# Booster_Main_Board.net
KiCad netlist of a schematic drawn in Altium Designer
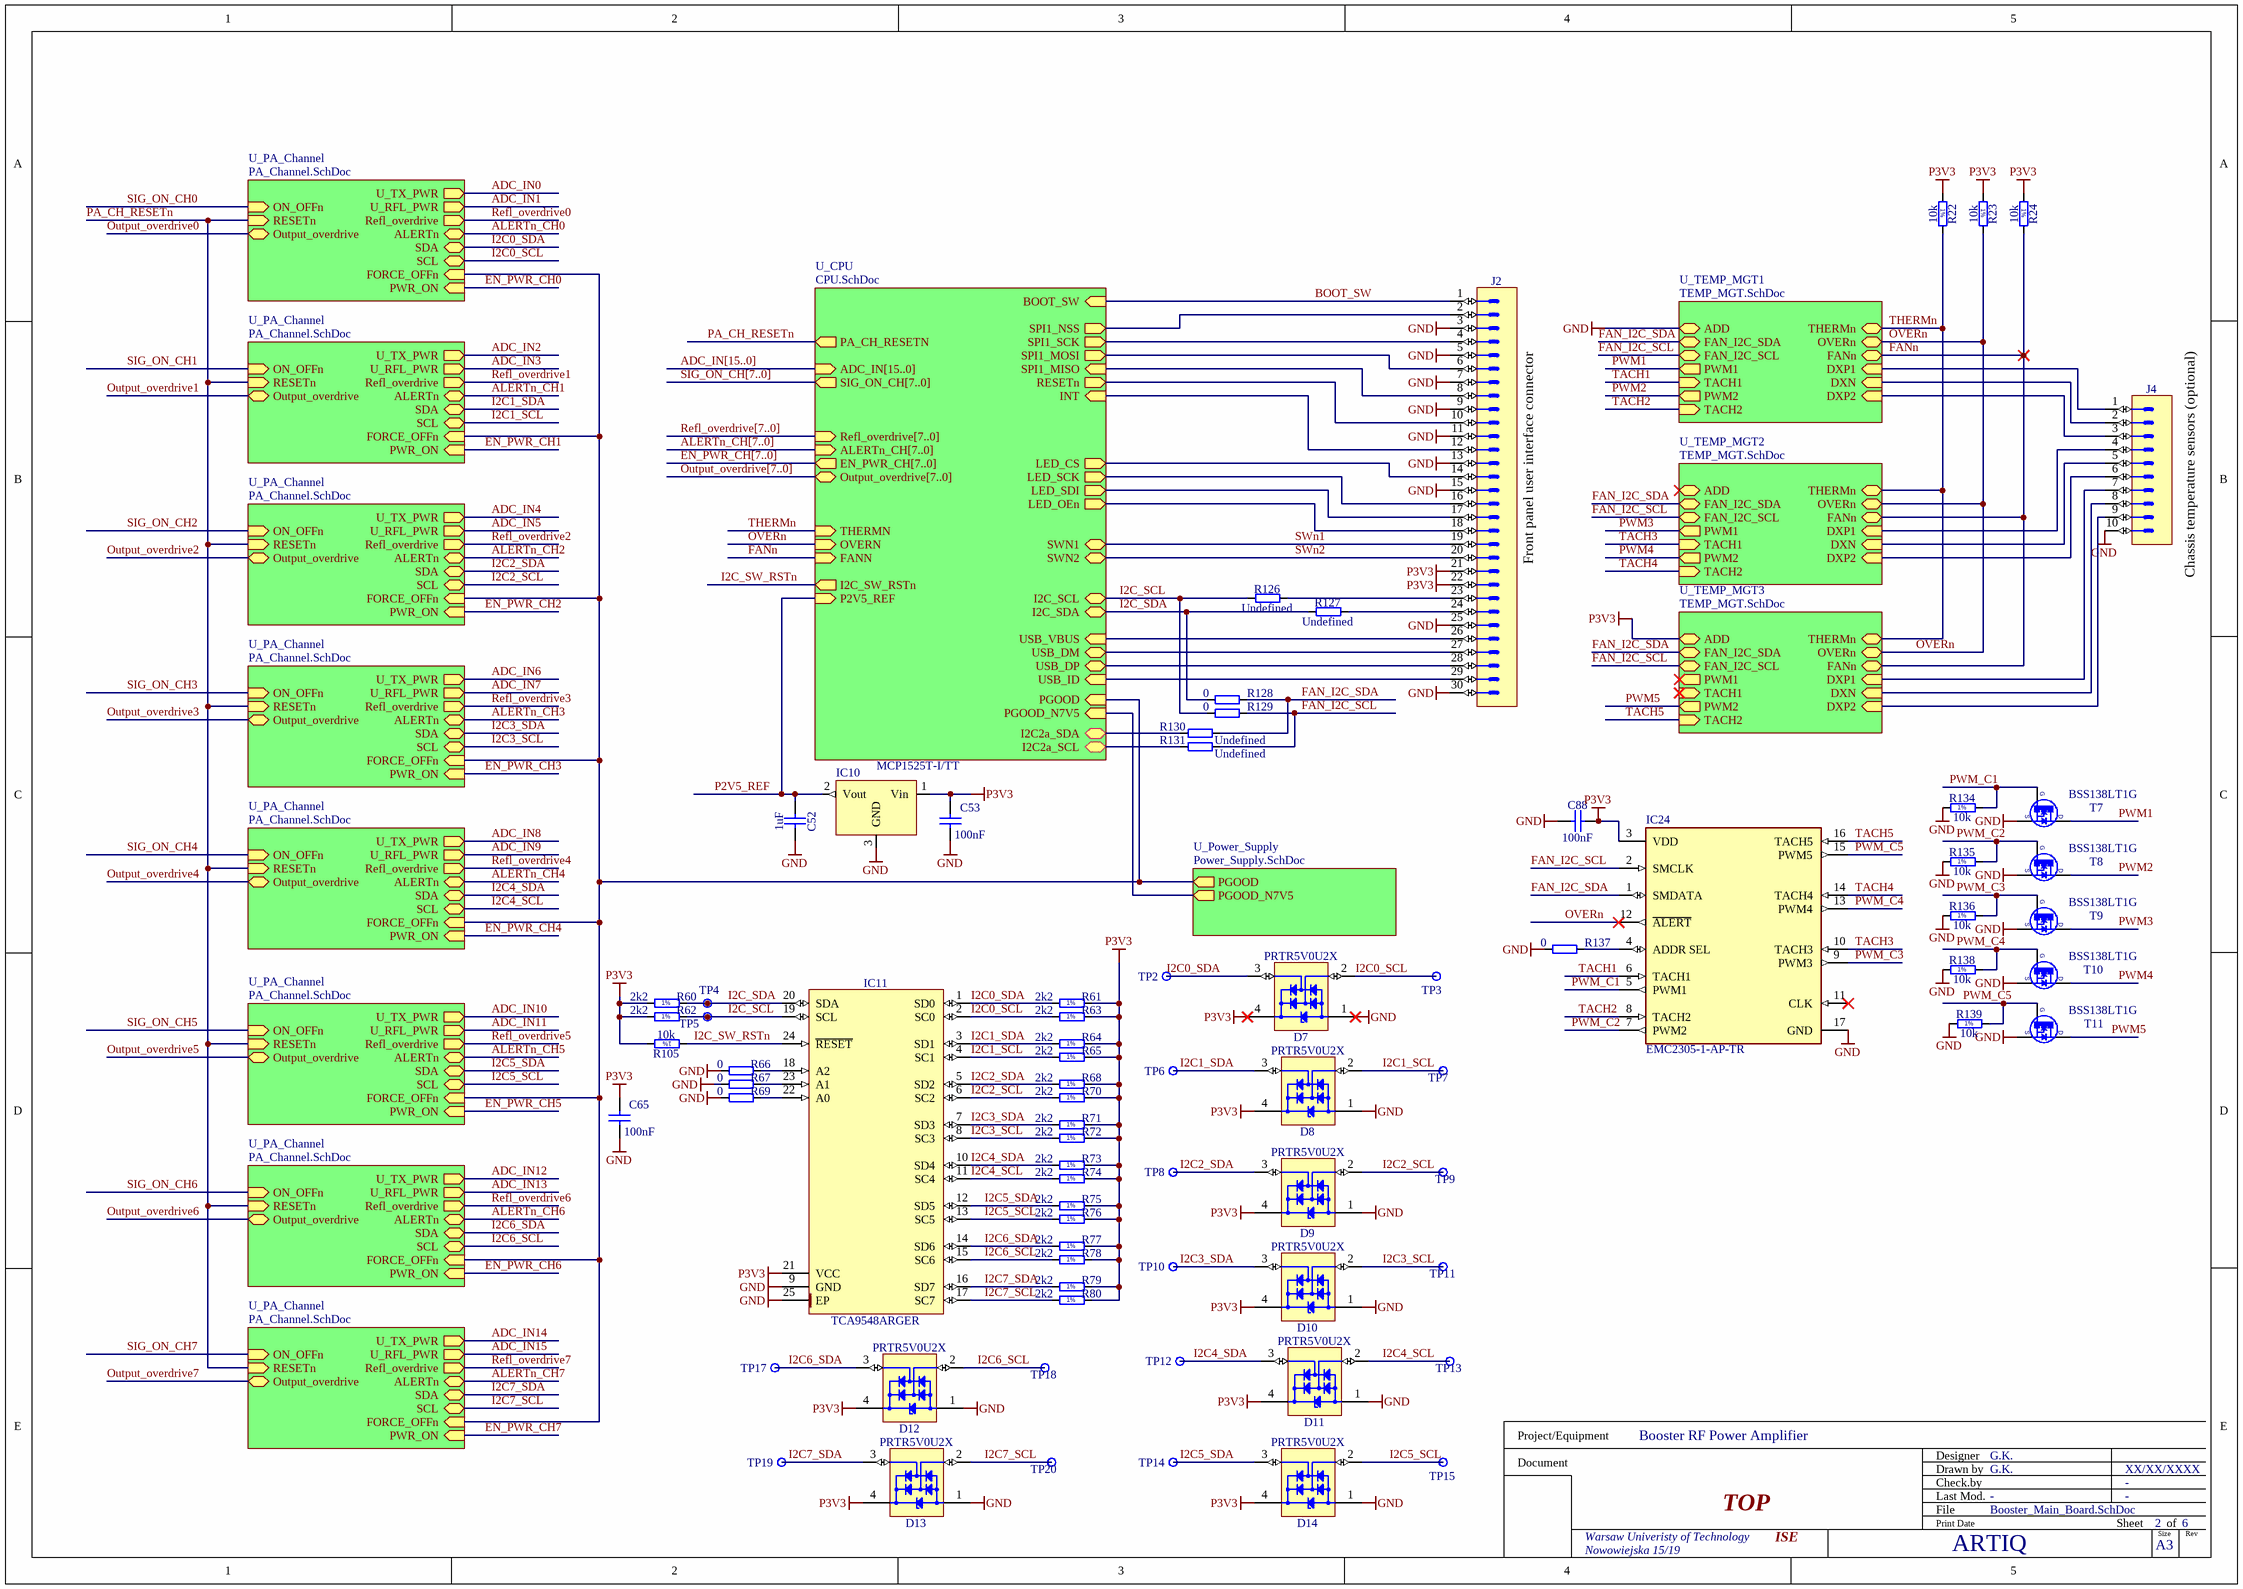
[diagram p0: Booster_Main_Board.SchDoc]

(export (version "E")
  (design (tool "Eeschema 10.0.6"))
  (components
    (comp (ref "C52")
      (value "1uF")
      (footprint "CAPC1005X55N")
      (description "Non-polarised capacitor")
      (fields
        (field (name "PART NUMBER") "CC0402_1UF_16V_10%_X5R")
        (field (name "VOLTAGE") "16V")
        (field (name "AUTHOR") "CERN DEM JLC")
      )
      (libsource (lib "Capacitors") (part "Capacitor - non polarized"))
    )
    (comp (ref "C53")
      (value "100nF")
      (footprint "CAPC1005X55N")
      (description "Non-polarised capacitor")
      (fields
        (field (name "PART NUMBER") "CC0402_100NF_16V_10%_X7R")
        (field (name "VOLTAGE") "16V")
        (field (name "AUTHOR") "CERN DEM JLC")
      )
      (libsource (lib "Capacitors") (part "Capacitor - non polarized"))
    )
    (comp (ref "C65")
      (value "100nF")
      (footprint "CAPC1005X55N")
      (description "Non-polarised capacitor")
      (fields
        (field (name "PART NUMBER") "CC0402_100NF_16V_10%_X7R")
        (field (name "VOLTAGE") "16V")
        (field (name "AUTHOR") "CERN DEM JLC")
      )
      (libsource (lib "Capacitors") (part "Capacitor - non polarized"))
    )
    (comp (ref "C88")
      (value "100nF")
      (footprint "CAPC1005X55N")
      (description "Non-polarised capacitor")
      (fields
        (field (name "PART NUMBER") "CC0402_100NF_16V_10%_X7R")
        (field (name "VOLTAGE") "16V")
        (field (name "AUTHOR") "CERN DEM JLC")
      )
      (libsource (lib "Capacitors") (part "Capacitor - non polarized"))
    )
    (comp (ref "D7")
      (value "PRTR5V0U2X")
      (footprint "SOT190P230X110-4N")
      (description "Ultra Low Capacitance Double Rail-to-Rail ESD Protection Diode")
      (fields
        (field (name "VOLTAGE") "5.5V")
        (field (name "MANUFACTURER") "NXP SEMICONDUCTORS")
        (field (name "AUTHOR") "CERN DEM JLC")
      )
      (libsource (lib "ICs And Semiconductors") (part "PRTR5V0U2X"))
    )
    (comp (ref "D8")
      (value "PRTR5V0U2X")
      (footprint "SOT190P230X110-4N")
      (description "Ultra Low Capacitance Double Rail-to-Rail ESD Protection Diode")
      (fields
        (field (name "VOLTAGE") "5.5V")
        (field (name "MANUFACTURER") "NXP SEMICONDUCTORS")
        (field (name "AUTHOR") "CERN DEM JLC")
      )
      (libsource (lib "ICs And Semiconductors") (part "PRTR5V0U2X"))
    )
    (comp (ref "D9")
      (value "PRTR5V0U2X")
      (footprint "SOT190P230X110-4N")
      (description "Ultra Low Capacitance Double Rail-to-Rail ESD Protection Diode")
      (fields
        (field (name "VOLTAGE") "5.5V")
        (field (name "MANUFACTURER") "NXP SEMICONDUCTORS")
        (field (name "AUTHOR") "CERN DEM JLC")
      )
      (libsource (lib "ICs And Semiconductors") (part "PRTR5V0U2X"))
    )
    (comp (ref "D10")
      (value "PRTR5V0U2X")
      (footprint "SOT190P230X110-4N")
      (description "Ultra Low Capacitance Double Rail-to-Rail ESD Protection Diode")
      (fields
        (field (name "VOLTAGE") "5.5V")
        (field (name "MANUFACTURER") "NXP SEMICONDUCTORS")
        (field (name "AUTHOR") "CERN DEM JLC")
      )
      (libsource (lib "ICs And Semiconductors") (part "PRTR5V0U2X"))
    )
    (comp (ref "D11")
      (value "PRTR5V0U2X")
      (footprint "SOT190P230X110-4N")
      (description "Ultra Low Capacitance Double Rail-to-Rail ESD Protection Diode")
      (fields
        (field (name "VOLTAGE") "5.5V")
        (field (name "MANUFACTURER") "NXP SEMICONDUCTORS")
        (field (name "AUTHOR") "CERN DEM JLC")
      )
      (libsource (lib "ICs And Semiconductors") (part "PRTR5V0U2X"))
    )
    (comp (ref "D12")
      (value "PRTR5V0U2X")
      (footprint "SOT190P230X110-4N")
      (description "Ultra Low Capacitance Double Rail-to-Rail ESD Protection Diode")
      (fields
        (field (name "VOLTAGE") "5.5V")
        (field (name "MANUFACTURER") "NXP SEMICONDUCTORS")
        (field (name "AUTHOR") "CERN DEM JLC")
      )
      (libsource (lib "ICs And Semiconductors") (part "PRTR5V0U2X"))
    )
    (comp (ref "D13")
      (value "PRTR5V0U2X")
      (footprint "SOT190P230X110-4N")
      (description "Ultra Low Capacitance Double Rail-to-Rail ESD Protection Diode")
      (fields
        (field (name "VOLTAGE") "5.5V")
        (field (name "MANUFACTURER") "NXP SEMICONDUCTORS")
        (field (name "AUTHOR") "CERN DEM JLC")
      )
      (libsource (lib "ICs And Semiconductors") (part "PRTR5V0U2X"))
    )
    (comp (ref "D14")
      (value "PRTR5V0U2X")
      (footprint "SOT190P230X110-4N")
      (description "Ultra Low Capacitance Double Rail-to-Rail ESD Protection Diode")
      (fields
        (field (name "VOLTAGE") "5.5V")
        (field (name "MANUFACTURER") "NXP SEMICONDUCTORS")
        (field (name "AUTHOR") "CERN DEM JLC")
      )
      (libsource (lib "ICs And Semiconductors") (part "PRTR5V0U2X"))
    )
    (comp (ref "IC10")
      (value "MCP1525T-I/TT")
      (footprint "SOT95P251X112-3N")
      (description "2.5 voltage reference")
      (libsource (lib "LIBRARY_SCH") (part "REF_MCP1525"))
    )
    (comp (ref "IC11")
      (value "TCA9548ARGER")
      (footprint "QFN50P400X400X100-25N-S220")
      (description "Low Voltage 8-Channel I2C Switch With Reset")
      (fields (field (name "MANUFACTURER") "TEXAS INSTRUMENTS") (field (name "AUTHOR") "CERN DEM JLC"))
      (libsource (lib "ICs And Semiconductors") (part "TCA9548ARGER"))
    )
    (comp (ref "IC24")
      (value "EMC2305-1-AP-TR")
      (footprint "FP-EMC2305-1-AP-TR-MFG")
      (description "IC MOTOR DRIVER 3V-3.6V 16QFN")
      (libsource (lib "Altium Content Vault") (part "344f2bb6cacff359c8bcd9507a07fb2"))
    )
    (comp (ref "J2")
      (value "~")
      (footprint "3M_N2530-6002RB")
      (description "Connector 30 Male")
      (fields
        (field (name "PART NUMBER") "3M_N2530-6002RB")
        (field (name "MANUFACTURER") "3M")
        (field (name "AUTHOR") "CERN DEM JLC")
      )
      (libsource (lib "Connectors") (part "Connector 30 Male"))
    )
    (comp (ref "J4")
      (value "Header 10")
      (footprint "3M_N2510-6003RB")
      (description "Connector 10 Male")
      (fields
        (field (name "PART NUMBER") "3M_N2510-6003RB")
        (field (name "MANUFACTURER") "3M")
        (field (name "AUTHOR") "CERN DEM JLC")
      )
      (libsource (lib "Connectors") (part "Connector 10 Male"))
    )
    (comp (ref "R22")
      (value "10k")
      (footprint "RESC1005X40N")
      (description "Resistor - 1%")
      (fields
        (field (name "PART NUMBER") "R0402_10K_1%_0.0625W_100PPM")
        (field (name "POWER") "0.0625W")
        (field (name "AUTHOR") "CERN DEM JLC")
      )
      (libsource (lib "Resistors") (part "Resistor - 1%"))
    )
    (comp (ref "R23")
      (value "10k")
      (footprint "RESC1005X40N")
      (description "Resistor - 1%")
      (fields
        (field (name "PART NUMBER") "R0402_10K_1%_0.0625W_100PPM")
        (field (name "POWER") "0.0625W")
        (field (name "AUTHOR") "CERN DEM JLC")
      )
      (libsource (lib "Resistors") (part "Resistor - 1%"))
    )
    (comp (ref "R24")
      (value "10k")
      (footprint "RESC1005X40N")
      (description "Resistor - 1%")
      (fields
        (field (name "PART NUMBER") "R0402_10K_1%_0.0625W_100PPM")
        (field (name "POWER") "0.0625W")
        (field (name "AUTHOR") "CERN DEM JLC")
      )
      (libsource (lib "Resistors") (part "Resistor - 1%"))
    )
    (comp (ref "R60")
      (value "2k2")
      (footprint "RESC1005X40N")
      (description "Resistor - 1%")
      (fields
        (field (name "PART NUMBER") "R0402_2K2_1%_0.0625W_100PPM")
        (field (name "POWER") "0.0625W")
        (field (name "AUTHOR") "CERN DEM JLC")
      )
      (libsource (lib "Resistors") (part "Resistor - 1%"))
    )
    (comp (ref "R61")
      (value "2k2")
      (footprint "RESC1005X40N")
      (description "Resistor - 1%")
      (fields
        (field (name "PART NUMBER") "R0402_2K2_1%_0.0625W_100PPM")
        (field (name "POWER") "0.0625W")
        (field (name "AUTHOR") "CERN DEM JLC")
      )
      (libsource (lib "Resistors") (part "Resistor - 1%"))
    )
    (comp (ref "R62")
      (value "2k2")
      (footprint "RESC1005X40N")
      (description "Resistor - 1%")
      (fields
        (field (name "PART NUMBER") "R0402_2K2_1%_0.0625W_100PPM")
        (field (name "POWER") "0.0625W")
        (field (name "AUTHOR") "CERN DEM JLC")
      )
      (libsource (lib "Resistors") (part "Resistor - 1%"))
    )
    (comp (ref "R63")
      (value "2k2")
      (footprint "RESC1005X40N")
      (description "Resistor - 1%")
      (fields
        (field (name "PART NUMBER") "R0402_2K2_1%_0.0625W_100PPM")
        (field (name "POWER") "0.0625W")
        (field (name "AUTHOR") "CERN DEM JLC")
      )
      (libsource (lib "Resistors") (part "Resistor - 1%"))
    )
    (comp (ref "R64")
      (value "2k2")
      (footprint "RESC1005X40N")
      (description "Resistor - 1%")
      (fields
        (field (name "PART NUMBER") "R0402_2K2_1%_0.0625W_100PPM")
        (field (name "POWER") "0.0625W")
        (field (name "AUTHOR") "CERN DEM JLC")
      )
      (libsource (lib "Resistors") (part "Resistor - 1%"))
    )
    (comp (ref "R65")
      (value "2k2")
      (footprint "RESC1005X40N")
      (description "Resistor - 1%")
      (fields
        (field (name "PART NUMBER") "R0402_2K2_1%_0.0625W_100PPM")
        (field (name "POWER") "0.0625W")
        (field (name "AUTHOR") "CERN DEM JLC")
      )
      (libsource (lib "Resistors") (part "Resistor - 1%"))
    )
    (comp (ref "R66")
      (value "0")
      (footprint "RESC1005X40N")
      (description "Resistor")
      (fields
        (field (name "PART NUMBER") "R0402_0R_JUMPER")
        (field (name "MANUFACTURER") "GENERIC")
        (field (name "AUTHOR") "CERN DEM JLC")
      )
      (libsource (lib "Resistors") (part "Resistor"))
    )
    (comp (ref "R67")
      (value "0")
      (footprint "RESC1005X40N")
      (description "Resistor")
      (fields
        (field (name "PART NUMBER") "R0402_0R_JUMPER")
        (field (name "MANUFACTURER") "GENERIC")
        (field (name "AUTHOR") "CERN DEM JLC")
      )
      (libsource (lib "Resistors") (part "Resistor"))
    )
    (comp (ref "R68")
      (value "2k2")
      (footprint "RESC1005X40N")
      (description "Resistor - 1%")
      (fields
        (field (name "PART NUMBER") "R0402_2K2_1%_0.0625W_100PPM")
        (field (name "POWER") "0.0625W")
        (field (name "AUTHOR") "CERN DEM JLC")
      )
      (libsource (lib "Resistors") (part "Resistor - 1%"))
    )
    (comp (ref "R69")
      (value "0")
      (footprint "RESC1005X40N")
      (description "Resistor")
      (fields
        (field (name "PART NUMBER") "R0402_0R_JUMPER")
        (field (name "MANUFACTURER") "GENERIC")
        (field (name "AUTHOR") "CERN DEM JLC")
      )
      (libsource (lib "Resistors") (part "Resistor"))
    )
    (comp (ref "R70")
      (value "2k2")
      (footprint "RESC1005X40N")
      (description "Resistor - 1%")
      (fields
        (field (name "PART NUMBER") "R0402_2K2_1%_0.0625W_100PPM")
        (field (name "POWER") "0.0625W")
        (field (name "AUTHOR") "CERN DEM JLC")
      )
      (libsource (lib "Resistors") (part "Resistor - 1%"))
    )
    (comp (ref "R71")
      (value "2k2")
      (footprint "RESC1005X40N")
      (description "Resistor - 1%")
      (fields
        (field (name "PART NUMBER") "R0402_2K2_1%_0.0625W_100PPM")
        (field (name "POWER") "0.0625W")
        (field (name "AUTHOR") "CERN DEM JLC")
      )
      (libsource (lib "Resistors") (part "Resistor - 1%"))
    )
    (comp (ref "R72")
      (value "2k2")
      (footprint "RESC1005X40N")
      (description "Resistor - 1%")
      (fields
        (field (name "PART NUMBER") "R0402_2K2_1%_0.0625W_100PPM")
        (field (name "POWER") "0.0625W")
        (field (name "AUTHOR") "CERN DEM JLC")
      )
      (libsource (lib "Resistors") (part "Resistor - 1%"))
    )
    (comp (ref "R73")
      (value "2k2")
      (footprint "RESC1005X40N")
      (description "Resistor - 1%")
      (fields
        (field (name "PART NUMBER") "R0402_2K2_1%_0.0625W_100PPM")
        (field (name "POWER") "0.0625W")
        (field (name "AUTHOR") "CERN DEM JLC")
      )
      (libsource (lib "Resistors") (part "Resistor - 1%"))
    )
    (comp (ref "R74")
      (value "2k2")
      (footprint "RESC1005X40N")
      (description "Resistor - 1%")
      (fields
        (field (name "PART NUMBER") "R0402_2K2_1%_0.0625W_100PPM")
        (field (name "POWER") "0.0625W")
        (field (name "AUTHOR") "CERN DEM JLC")
      )
      (libsource (lib "Resistors") (part "Resistor - 1%"))
    )
    (comp (ref "R75")
      (value "2k2")
      (footprint "RESC1005X40N")
      (description "Resistor - 1%")
      (fields
        (field (name "PART NUMBER") "R0402_2K2_1%_0.0625W_100PPM")
        (field (name "POWER") "0.0625W")
        (field (name "AUTHOR") "CERN DEM JLC")
      )
      (libsource (lib "Resistors") (part "Resistor - 1%"))
    )
    (comp (ref "R76")
      (value "2k2")
      (footprint "RESC1005X40N")
      (description "Resistor - 1%")
      (fields
        (field (name "PART NUMBER") "R0402_2K2_1%_0.0625W_100PPM")
        (field (name "POWER") "0.0625W")
        (field (name "AUTHOR") "CERN DEM JLC")
      )
      (libsource (lib "Resistors") (part "Resistor - 1%"))
    )
    (comp (ref "R77")
      (value "2k2")
      (footprint "RESC1005X40N")
      (description "Resistor - 1%")
      (fields
        (field (name "PART NUMBER") "R0402_2K2_1%_0.0625W_100PPM")
        (field (name "POWER") "0.0625W")
        (field (name "AUTHOR") "CERN DEM JLC")
      )
      (libsource (lib "Resistors") (part "Resistor - 1%"))
    )
    (comp (ref "R78")
      (value "2k2")
      (footprint "RESC1005X40N")
      (description "Resistor - 1%")
      (fields
        (field (name "PART NUMBER") "R0402_2K2_1%_0.0625W_100PPM")
        (field (name "POWER") "0.0625W")
        (field (name "AUTHOR") "CERN DEM JLC")
      )
      (libsource (lib "Resistors") (part "Resistor - 1%"))
    )
    (comp (ref "R79")
      (value "2k2")
      (footprint "RESC1005X40N")
      (description "Resistor - 1%")
      (fields
        (field (name "PART NUMBER") "R0402_2K2_1%_0.0625W_100PPM")
        (field (name "POWER") "0.0625W")
        (field (name "AUTHOR") "CERN DEM JLC")
      )
      (libsource (lib "Resistors") (part "Resistor - 1%"))
    )
    (comp (ref "R80")
      (value "2k2")
      (footprint "RESC1005X40N")
      (description "Resistor - 1%")
      (fields
        (field (name "PART NUMBER") "R0402_2K2_1%_0.0625W_100PPM")
        (field (name "POWER") "0.0625W")
        (field (name "AUTHOR") "CERN DEM JLC")
      )
      (libsource (lib "Resistors") (part "Resistor - 1%"))
    )
    (comp (ref "R105")
      (value "10k")
      (footprint "RESC1005X40N")
      (description "Resistor - 1%")
      (fields
        (field (name "PART NUMBER") "R0402_10K_1%_0.0625W_100PPM")
        (field (name "POWER") "0.0625W")
        (field (name "AUTHOR") "CERN DEM JLC")
      )
      (libsource (lib "Resistors") (part "Resistor - 1%"))
    )
    (comp (ref "R126")
      (value "Undefined")
      (footprint "RESC1005X40N")
      (description "Resistor")
      (fields (field (name "PART NUMBER") "R0402_NO-VALUE") (field (name "AUTHOR") "CERN DEM JLC"))
      (libsource (lib "Resistors") (part "Resistor"))
    )
    (comp (ref "R127")
      (value "Undefined")
      (footprint "RESC1005X40N")
      (description "Resistor")
      (fields (field (name "PART NUMBER") "R0402_NO-VALUE") (field (name "AUTHOR") "CERN DEM JLC"))
      (libsource (lib "Resistors") (part "Resistor"))
    )
    (comp (ref "R128")
      (value "0")
      (footprint "RESC1005X40N")
      (description "Resistor")
      (fields
        (field (name "PART NUMBER") "R0402_0R_JUMPER")
        (field (name "MANUFACTURER") "GENERIC")
        (field (name "AUTHOR") "CERN DEM JLC")
      )
      (libsource (lib "Resistors") (part "Resistor"))
    )
    (comp (ref "R129")
      (value "0")
      (footprint "RESC1005X40N")
      (description "Resistor")
      (fields
        (field (name "PART NUMBER") "R0402_0R_JUMPER")
        (field (name "MANUFACTURER") "GENERIC")
        (field (name "AUTHOR") "CERN DEM JLC")
      )
      (libsource (lib "Resistors") (part "Resistor"))
    )
    (comp (ref "R130")
      (value "Undefined")
      (footprint "RESC1005X40N")
      (description "Resistor")
      (fields (field (name "PART NUMBER") "R0402_NO-VALUE") (field (name "AUTHOR") "CERN DEM JLC"))
      (libsource (lib "Resistors") (part "Resistor"))
    )
    (comp (ref "R131")
      (value "Undefined")
      (footprint "RESC1005X40N")
      (description "Resistor")
      (fields (field (name "PART NUMBER") "R0402_NO-VALUE") (field (name "AUTHOR") "CERN DEM JLC"))
      (libsource (lib "Resistors") (part "Resistor"))
    )
    (comp (ref "R134")
      (value "10k")
      (footprint "RESC1005X40N")
      (description "Resistor - 1%")
      (fields
        (field (name "PART NUMBER") "R0402_10K_1%_0.0625W_100PPM")
        (field (name "POWER") "0.0625W")
        (field (name "AUTHOR") "CERN DEM JLC")
      )
      (libsource (lib "Resistors") (part "Resistor - 1%"))
    )
    (comp (ref "R135")
      (value "10k")
      (footprint "RESC1005X40N")
      (description "Resistor - 1%")
      (fields
        (field (name "PART NUMBER") "R0402_10K_1%_0.0625W_100PPM")
        (field (name "POWER") "0.0625W")
        (field (name "AUTHOR") "CERN DEM JLC")
      )
      (libsource (lib "Resistors") (part "Resistor - 1%"))
    )
    (comp (ref "R136")
      (value "10k")
      (footprint "RESC1005X40N")
      (description "Resistor - 1%")
      (fields
        (field (name "PART NUMBER") "R0402_10K_1%_0.0625W_100PPM")
        (field (name "POWER") "0.0625W")
        (field (name "AUTHOR") "CERN DEM JLC")
      )
      (libsource (lib "Resistors") (part "Resistor - 1%"))
    )
    (comp (ref "R137")
      (value "0")
      (footprint "RESC1005X40N")
      (description "Resistor")
      (fields
        (field (name "PART NUMBER") "R0402_0R_JUMPER")
        (field (name "MANUFACTURER") "GENERIC")
        (field (name "AUTHOR") "CERN DEM JLC")
      )
      (libsource (lib "Resistors") (part "Resistor"))
    )
    (comp (ref "R138")
      (value "10k")
      (footprint "RESC1005X40N")
      (description "Resistor - 1%")
      (fields
        (field (name "PART NUMBER") "R0402_10K_1%_0.0625W_100PPM")
        (field (name "POWER") "0.0625W")
        (field (name "AUTHOR") "CERN DEM JLC")
      )
      (libsource (lib "Resistors") (part "Resistor - 1%"))
    )
    (comp (ref "R139")
      (value "10k")
      (footprint "RESC1005X40N")
      (description "Resistor - 1%")
      (fields
        (field (name "PART NUMBER") "R0402_10K_1%_0.0625W_100PPM")
        (field (name "POWER") "0.0625W")
        (field (name "AUTHOR") "CERN DEM JLC")
      )
      (libsource (lib "Resistors") (part "Resistor - 1%"))
    )
    (comp (ref "T7")
      (value "BSS138LT1G")
      (footprint "SOT95P240X110-3N")
      (description "N-CHANNEL MOSFET WITH DIODE")
      (fields (field (name "MANUFACTURER") "ON SEMICONDUCTOR") (field (name "AUTHOR") "CERN DEM JLC"))
      (libsource (lib "ICs And Semiconductors") (part "N-MOSFET-D 1G 2S 3D"))
    )
    (comp (ref "T8")
      (value "BSS138LT1G")
      (footprint "SOT95P240X110-3N")
      (description "N-CHANNEL MOSFET WITH DIODE")
      (fields (field (name "MANUFACTURER") "ON SEMICONDUCTOR") (field (name "AUTHOR") "CERN DEM JLC"))
      (libsource (lib "ICs And Semiconductors") (part "N-MOSFET-D 1G 2S 3D"))
    )
    (comp (ref "T9")
      (value "BSS138LT1G")
      (footprint "SOT95P240X110-3N")
      (description "N-CHANNEL MOSFET WITH DIODE")
      (fields (field (name "MANUFACTURER") "ON SEMICONDUCTOR") (field (name "AUTHOR") "CERN DEM JLC"))
      (libsource (lib "ICs And Semiconductors") (part "N-MOSFET-D 1G 2S 3D"))
    )
    (comp (ref "T10")
      (value "BSS138LT1G")
      (footprint "SOT95P240X110-3N")
      (description "N-CHANNEL MOSFET WITH DIODE")
      (fields (field (name "MANUFACTURER") "ON SEMICONDUCTOR") (field (name "AUTHOR") "CERN DEM JLC"))
      (libsource (lib "ICs And Semiconductors") (part "N-MOSFET-D 1G 2S 3D"))
    )
    (comp (ref "T11")
      (value "BSS138LT1G")
      (footprint "SOT95P240X110-3N")
      (description "N-CHANNEL MOSFET WITH DIODE")
      (fields (field (name "MANUFACTURER") "ON SEMICONDUCTOR") (field (name "AUTHOR") "CERN DEM JLC"))
      (libsource (lib "ICs And Semiconductors") (part "N-MOSFET-D 1G 2S 3D"))
    )
    (comp (ref "TP2")
      (value "Test Point")
      (footprint "TPS127")
      (fields (field (name "PART NUMBER") "SMD_PAD_1.27X1.27MM") (field (name "AUTHOR") "CERN DEM JLC"))
      (libsource (lib "Eletro-mechanical") (part "Test Point"))
    )
    (comp (ref "TP3")
      (value "Test Point")
      (footprint "TPS127")
      (fields (field (name "PART NUMBER") "SMD_PAD_1.27X1.27MM") (field (name "AUTHOR") "CERN DEM JLC"))
      (libsource (lib "Eletro-mechanical") (part "Test Point"))
    )
    (comp (ref "TP4")
      (value "Test Point")
      (footprint "TPS127")
      (fields (field (name "PART NUMBER") "SMD_PAD_1.27X1.27MM") (field (name "AUTHOR") "CERN DEM JLC"))
      (libsource (lib "Eletro-mechanical") (part "Test Point"))
    )
    (comp (ref "TP5")
      (value "Test Point")
      (footprint "TPS127")
      (fields (field (name "PART NUMBER") "SMD_PAD_1.27X1.27MM") (field (name "AUTHOR") "CERN DEM JLC"))
      (libsource (lib "Eletro-mechanical") (part "Test Point"))
    )
    (comp (ref "TP6")
      (value "Test Point")
      (footprint "TPS127")
      (fields (field (name "PART NUMBER") "SMD_PAD_1.27X1.27MM") (field (name "AUTHOR") "CERN DEM JLC"))
      (libsource (lib "Eletro-mechanical") (part "Test Point"))
    )
    (comp (ref "TP7")
      (value "Test Point")
      (footprint "TPS127")
      (fields (field (name "PART NUMBER") "SMD_PAD_1.27X1.27MM") (field (name "AUTHOR") "CERN DEM JLC"))
      (libsource (lib "Eletro-mechanical") (part "Test Point"))
    )
    (comp (ref "TP8")
      (value "Test Point")
      (footprint "TPS127")
      (fields (field (name "PART NUMBER") "SMD_PAD_1.27X1.27MM") (field (name "AUTHOR") "CERN DEM JLC"))
      (libsource (lib "Eletro-mechanical") (part "Test Point"))
    )
    (comp (ref "TP9")
      (value "Test Point")
      (footprint "TPS127")
      (fields (field (name "PART NUMBER") "SMD_PAD_1.27X1.27MM") (field (name "AUTHOR") "CERN DEM JLC"))
      (libsource (lib "Eletro-mechanical") (part "Test Point"))
    )
    (comp (ref "TP10")
      (value "Test Point")
      (footprint "TPS127")
      (fields (field (name "PART NUMBER") "SMD_PAD_1.27X1.27MM") (field (name "AUTHOR") "CERN DEM JLC"))
      (libsource (lib "Eletro-mechanical") (part "Test Point"))
    )
    (comp (ref "TP11")
      (value "Test Point")
      (footprint "TPS127")
      (fields (field (name "PART NUMBER") "SMD_PAD_1.27X1.27MM") (field (name "AUTHOR") "CERN DEM JLC"))
      (libsource (lib "Eletro-mechanical") (part "Test Point"))
    )
    (comp (ref "TP12")
      (value "Test Point")
      (footprint "TPS127")
      (fields (field (name "PART NUMBER") "SMD_PAD_1.27X1.27MM") (field (name "AUTHOR") "CERN DEM JLC"))
      (libsource (lib "Eletro-mechanical") (part "Test Point"))
    )
    (comp (ref "TP13")
      (value "Test Point")
      (footprint "TPS127")
      (fields (field (name "PART NUMBER") "SMD_PAD_1.27X1.27MM") (field (name "AUTHOR") "CERN DEM JLC"))
      (libsource (lib "Eletro-mechanical") (part "Test Point"))
    )
    (comp (ref "TP14")
      (value "Test Point")
      (footprint "TPS127")
      (fields (field (name "PART NUMBER") "SMD_PAD_1.27X1.27MM") (field (name "AUTHOR") "CERN DEM JLC"))
      (libsource (lib "Eletro-mechanical") (part "Test Point"))
    )
    (comp (ref "TP15")
      (value "Test Point")
      (footprint "TPS127")
      (fields (field (name "PART NUMBER") "SMD_PAD_1.27X1.27MM") (field (name "AUTHOR") "CERN DEM JLC"))
      (libsource (lib "Eletro-mechanical") (part "Test Point"))
    )
    (comp (ref "TP17")
      (value "Test Point")
      (footprint "TPS127")
      (fields (field (name "PART NUMBER") "SMD_PAD_1.27X1.27MM") (field (name "AUTHOR") "CERN DEM JLC"))
      (libsource (lib "Eletro-mechanical") (part "Test Point"))
    )
    (comp (ref "TP18")
      (value "Test Point")
      (footprint "TPS127")
      (fields (field (name "PART NUMBER") "SMD_PAD_1.27X1.27MM") (field (name "AUTHOR") "CERN DEM JLC"))
      (libsource (lib "Eletro-mechanical") (part "Test Point"))
    )
    (comp (ref "TP19")
      (value "Test Point")
      (footprint "TPS127")
      (fields (field (name "PART NUMBER") "SMD_PAD_1.27X1.27MM") (field (name "AUTHOR") "CERN DEM JLC"))
      (libsource (lib "Eletro-mechanical") (part "Test Point"))
    )
    (comp (ref "TP20")
      (value "Test Point")
      (footprint "TPS127")
      (fields (field (name "PART NUMBER") "SMD_PAD_1.27X1.27MM") (field (name "AUTHOR") "CERN DEM JLC"))
      (libsource (lib "Eletro-mechanical") (part "Test Point"))
    )
  )
  (nets
    (net (code "28") (name "/BOOT_SW") (class "Default")
      (node (ref "J2") (pin "1") (pinfunction "1_1") (pintype "bidirectional"))
    )
    (net (code "29") (name "/DXN") (class "Default")
      (node (ref "J4") (pin "5") (pinfunction "5_5") (pintype "bidirectional"))
    )
    (net (code "30") (name "/DXN_1") (class "Default")
      (node (ref "J4") (pin "8") (pinfunction "8_8") (pintype "bidirectional"))
    )
    (net (code "31") (name "/DXN_2") (class "Default")
      (node (ref "J4") (pin "2") (pinfunction "2_2") (pintype "bidirectional"))
    )
    (net (code "32") (name "/DXP1") (class "Default")
      (node (ref "J4") (pin "4") (pinfunction "4_4") (pintype "bidirectional"))
    )
    (net (code "33") (name "/DXP1_1") (class "Default")
      (node (ref "J4") (pin "7") (pinfunction "7_7") (pintype "bidirectional"))
    )
    (net (code "34") (name "/DXP1_2") (class "Default")
      (node (ref "J4") (pin "1") (pinfunction "1_1") (pintype "bidirectional"))
    )
    (net (code "35") (name "/DXP2") (class "Default")
      (node (ref "J4") (pin "6") (pinfunction "6_6") (pintype "bidirectional"))
    )
    (net (code "36") (name "/DXP2_1") (class "Default")
      (node (ref "J4") (pin "9") (pinfunction "9_9") (pintype "bidirectional"))
    )
    (net (code "37") (name "/DXP2_2") (class "Default")
      (node (ref "J4") (pin "3") (pinfunction "3_3") (pintype "bidirectional"))
    )
    (net (code "47") (name "/FAN_I2C_SCL") (class "Default")
      (node (ref "IC24") (pin "2") (pinfunction "SMCLK_2") (pintype "input"))
      (node (ref "R129") (pin "2") (pinfunction "2_2") (pintype "passive"))
      (node (ref "R131") (pin "2") (pinfunction "2_2") (pintype "passive"))
    )
    (net (code "48") (name "/FAN_I2C_SDA") (class "Default")
      (node (ref "IC24") (pin "1") (pinfunction "SMDATA_1") (pintype "bidirectional"))
      (node (ref "R128") (pin "2") (pinfunction "2_2") (pintype "passive"))
      (node (ref "R130") (pin "2") (pinfunction "2_2") (pintype "passive"))
    )
    (net (code "49") (name "/FANn") (class "Default")
      (node (ref "R24") (pin "2") (pinfunction "2_2") (pintype "passive"))
    )
    (net (code "50") (name "/I2C0_SCL") (class "Default")
      (node (ref "D7") (pin "2") (pinfunction "I/O1_2") (pintype "bidirectional"))
      (node (ref "IC11") (pin "2") (pinfunction "SC0_2") (pintype "bidirectional"))
      (node (ref "R63") (pin "1") (pinfunction "1_1") (pintype "passive"))
      (node (ref "TP3") (pin "1") (pinfunction "1_1") (pintype "bidirectional"))
    )
    (net (code "51") (name "/I2C0_SDA") (class "Default")
      (node (ref "D7") (pin "3") (pinfunction "I/O2_3") (pintype "bidirectional"))
      (node (ref "IC11") (pin "1") (pinfunction "SD0_1") (pintype "bidirectional"))
      (node (ref "R61") (pin "1") (pinfunction "1_1") (pintype "passive"))
      (node (ref "TP2") (pin "1") (pinfunction "1_1") (pintype "bidirectional"))
    )
    (net (code "52") (name "/I2C1_SCL") (class "Default")
      (node (ref "D8") (pin "2") (pinfunction "I/O1_2") (pintype "bidirectional"))
      (node (ref "IC11") (pin "4") (pinfunction "SC1_4") (pintype "bidirectional"))
      (node (ref "R65") (pin "1") (pinfunction "1_1") (pintype "passive"))
      (node (ref "TP7") (pin "1") (pinfunction "1_1") (pintype "bidirectional"))
    )
    (net (code "53") (name "/I2C1_SDA") (class "Default")
      (node (ref "D8") (pin "3") (pinfunction "I/O2_3") (pintype "bidirectional"))
      (node (ref "IC11") (pin "3") (pinfunction "SD1_3") (pintype "bidirectional"))
      (node (ref "R64") (pin "1") (pinfunction "1_1") (pintype "passive"))
      (node (ref "TP6") (pin "1") (pinfunction "1_1") (pintype "bidirectional"))
    )
    (net (code "54") (name "/I2C2_SCL") (class "Default")
      (node (ref "D9") (pin "2") (pinfunction "I/O1_2") (pintype "bidirectional"))
      (node (ref "IC11") (pin "6") (pinfunction "SC2_6") (pintype "bidirectional"))
      (node (ref "R70") (pin "1") (pinfunction "1_1") (pintype "passive"))
      (node (ref "TP9") (pin "1") (pinfunction "1_1") (pintype "bidirectional"))
    )
    (net (code "55") (name "/I2C2_SDA") (class "Default")
      (node (ref "D9") (pin "3") (pinfunction "I/O2_3") (pintype "bidirectional"))
      (node (ref "IC11") (pin "5") (pinfunction "SD2_5") (pintype "bidirectional"))
      (node (ref "R68") (pin "1") (pinfunction "1_1") (pintype "passive"))
      (node (ref "TP8") (pin "1") (pinfunction "1_1") (pintype "bidirectional"))
    )
    (net (code "56") (name "/I2C2a_SCL") (class "Default")
      (node (ref "R131") (pin "1") (pinfunction "1_1") (pintype "passive"))
    )
    (net (code "57") (name "/I2C2a_SDA") (class "Default")
      (node (ref "R130") (pin "1") (pinfunction "1_1") (pintype "passive"))
    )
    (net (code "58") (name "/I2C3_SCL") (class "Default")
      (node (ref "D10") (pin "2") (pinfunction "I/O1_2") (pintype "bidirectional"))
      (node (ref "IC11") (pin "8") (pinfunction "SC3_8") (pintype "bidirectional"))
      (node (ref "R72") (pin "1") (pinfunction "1_1") (pintype "passive"))
      (node (ref "TP11") (pin "1") (pinfunction "1_1") (pintype "bidirectional"))
    )
    (net (code "59") (name "/I2C3_SDA") (class "Default")
      (node (ref "D10") (pin "3") (pinfunction "I/O2_3") (pintype "bidirectional"))
      (node (ref "IC11") (pin "7") (pinfunction "SD3_7") (pintype "bidirectional"))
      (node (ref "R71") (pin "1") (pinfunction "1_1") (pintype "passive"))
      (node (ref "TP10") (pin "1") (pinfunction "1_1") (pintype "bidirectional"))
    )
    (net (code "60") (name "/I2C4_SCL") (class "Default")
      (node (ref "D11") (pin "2") (pinfunction "I/O1_2") (pintype "bidirectional"))
      (node (ref "IC11") (pin "11") (pinfunction "SC4_11") (pintype "bidirectional"))
      (node (ref "R74") (pin "1") (pinfunction "1_1") (pintype "passive"))
      (node (ref "TP13") (pin "1") (pinfunction "1_1") (pintype "bidirectional"))
    )
    (net (code "61") (name "/I2C4_SDA") (class "Default")
      (node (ref "D11") (pin "3") (pinfunction "I/O2_3") (pintype "bidirectional"))
      (node (ref "IC11") (pin "10") (pinfunction "SD4_10") (pintype "bidirectional"))
      (node (ref "R73") (pin "1") (pinfunction "1_1") (pintype "passive"))
      (node (ref "TP12") (pin "1") (pinfunction "1_1") (pintype "bidirectional"))
    )
    (net (code "62") (name "/I2C5_SCL") (class "Default")
      (node (ref "D14") (pin "2") (pinfunction "I/O1_2") (pintype "bidirectional"))
      (node (ref "IC11") (pin "13") (pinfunction "SC5_13") (pintype "bidirectional"))
      (node (ref "R76") (pin "1") (pinfunction "1_1") (pintype "passive"))
      (node (ref "TP15") (pin "1") (pinfunction "1_1") (pintype "bidirectional"))
    )
    (net (code "63") (name "/I2C5_SDA") (class "Default")
      (node (ref "D14") (pin "3") (pinfunction "I/O2_3") (pintype "bidirectional"))
      (node (ref "IC11") (pin "12") (pinfunction "SD5_12") (pintype "bidirectional"))
      (node (ref "R75") (pin "1") (pinfunction "1_1") (pintype "passive"))
      (node (ref "TP14") (pin "1") (pinfunction "1_1") (pintype "bidirectional"))
    )
    (net (code "64") (name "/I2C6_SCL") (class "Default")
      (node (ref "D12") (pin "2") (pinfunction "I/O1_2") (pintype "bidirectional"))
      (node (ref "IC11") (pin "15") (pinfunction "SC6_15") (pintype "bidirectional"))
      (node (ref "R78") (pin "1") (pinfunction "1_1") (pintype "passive"))
      (node (ref "TP18") (pin "1") (pinfunction "1_1") (pintype "bidirectional"))
    )
    (net (code "65") (name "/I2C6_SDA") (class "Default")
      (node (ref "D12") (pin "3") (pinfunction "I/O2_3") (pintype "bidirectional"))
      (node (ref "IC11") (pin "14") (pinfunction "SD6_14") (pintype "bidirectional"))
      (node (ref "R77") (pin "1") (pinfunction "1_1") (pintype "passive"))
      (node (ref "TP17") (pin "1") (pinfunction "1_1") (pintype "bidirectional"))
    )
    (net (code "66") (name "/I2C7_SCL") (class "Default")
      (node (ref "D13") (pin "2") (pinfunction "I/O1_2") (pintype "bidirectional"))
      (node (ref "IC11") (pin "17") (pinfunction "SC7_17") (pintype "bidirectional"))
      (node (ref "R80") (pin "1") (pinfunction "1_1") (pintype "passive"))
      (node (ref "TP20") (pin "1") (pinfunction "1_1") (pintype "bidirectional"))
    )
    (net (code "67") (name "/I2C7_SDA") (class "Default")
      (node (ref "D13") (pin "3") (pinfunction "I/O2_3") (pintype "bidirectional"))
      (node (ref "IC11") (pin "16") (pinfunction "SD7_16") (pintype "bidirectional"))
      (node (ref "R79") (pin "1") (pinfunction "1_1") (pintype "passive"))
      (node (ref "TP19") (pin "1") (pinfunction "1_1") (pintype "bidirectional"))
    )
    (net (code "68") (name "/I2C_SCL") (class "Default")
      (node (ref "IC11") (pin "19") (pinfunction "SCL_19") (pintype "bidirectional"))
      (node (ref "R126") (pin "1") (pinfunction "1_1") (pintype "passive"))
      (node (ref "R129") (pin "1") (pinfunction "1_1") (pintype "passive"))
      (node (ref "R62") (pin "2") (pinfunction "2_2") (pintype "passive"))
      (node (ref "TP5") (pin "1") (pinfunction "1_1") (pintype "bidirectional"))
    )
    (net (code "69") (name "/I2C_SDA") (class "Default")
      (node (ref "IC11") (pin "20") (pinfunction "SDA_20") (pintype "bidirectional"))
      (node (ref "R127") (pin "1") (pinfunction "1_1") (pintype "passive"))
      (node (ref "R128") (pin "1") (pinfunction "1_1") (pintype "passive"))
      (node (ref "R60") (pin "2") (pinfunction "2_2") (pintype "passive"))
      (node (ref "TP4") (pin "1") (pinfunction "1_1") (pintype "bidirectional"))
    )
    (net (code "70") (name "/I2C_SW_RSTn") (class "Default")
      (node (ref "IC11") (pin "24") (pinfunction "~{RESET}_24") (pintype "input"))
      (node (ref "R105") (pin "1") (pinfunction "1_1") (pintype "passive"))
    )
    (net (code "71") (name "/INT") (class "Default")
      (node (ref "J2") (pin "12") (pinfunction "12_12") (pintype "bidirectional"))
    )
    (net (code "72") (name "/LED_CS") (class "Default")
      (node (ref "J2") (pin "14") (pinfunction "14_14") (pintype "bidirectional"))
    )
    (net (code "73") (name "/LED_OEn") (class "Default")
      (node (ref "J2") (pin "18") (pinfunction "18_18") (pintype "bidirectional"))
    )
    (net (code "74") (name "/LED_SCK") (class "Default")
      (node (ref "J2") (pin "16") (pinfunction "16_16") (pintype "bidirectional"))
    )
    (net (code "75") (name "/LED_SDI") (class "Default")
      (node (ref "J2") (pin "17") (pinfunction "17_17") (pintype "bidirectional"))
    )
    (net (code "76") (name "/OVERn") (class "Default")
      (node (ref "IC24") (pin "12") (pinfunction "~{ALERT}_12") (pintype "output"))
      (node (ref "R23") (pin "2") (pinfunction "2_2") (pintype "passive"))
    )
    (net (code "86") (name "/P2V5_REF") (class "Default")
      (node (ref "C52") (pin "1") (pinfunction "1_1") (pintype "passive"))
      (node (ref "IC10") (pin "2") (pinfunction "Vout_2") (pintype "output"))
    )
    (net (code "90") (name "/PWM1") (class "Default")
      (node (ref "T7") (pin "3") (pinfunction "D_3") (pintype "passive"))
    )
    (net (code "92") (name "/PWM2") (class "Default")
      (node (ref "T8") (pin "3") (pinfunction "D_3") (pintype "passive"))
    )
    (net (code "93") (name "/PWM3") (class "Default")
      (node (ref "T9") (pin "3") (pinfunction "D_3") (pintype "passive"))
    )
    (net (code "94") (name "/PWM4") (class "Default")
      (node (ref "T10") (pin "3") (pinfunction "D_3") (pintype "passive"))
    )
    (net (code "95") (name "/PWM5") (class "Default")
      (node (ref "T11") (pin "3") (pinfunction "D_3") (pintype "passive"))
    )
    (net (code "96") (name "/PWM_C1") (class "Default")
      (node (ref "IC24") (pin "5") (pinfunction "PWM1_5") (pintype "output"))
      (node (ref "R134") (pin "2") (pinfunction "2_2") (pintype "passive"))
      (node (ref "T7") (pin "1") (pinfunction "G_1") (pintype "passive"))
    )
    (net (code "97") (name "/PWM_C2") (class "Default")
      (node (ref "IC24") (pin "7") (pinfunction "PWM2_7") (pintype "output"))
      (node (ref "R135") (pin "2") (pinfunction "2_2") (pintype "passive"))
      (node (ref "T8") (pin "1") (pinfunction "G_1") (pintype "passive"))
    )
    (net (code "98") (name "/PWM_C3") (class "Default")
      (node (ref "IC24") (pin "9") (pinfunction "PWM3_9") (pintype "output"))
      (node (ref "R136") (pin "2") (pinfunction "2_2") (pintype "passive"))
      (node (ref "T9") (pin "1") (pinfunction "G_1") (pintype "passive"))
    )
    (net (code "99") (name "/PWM_C4") (class "Default")
      (node (ref "IC24") (pin "13") (pinfunction "PWM4_13") (pintype "output"))
      (node (ref "R138") (pin "2") (pinfunction "2_2") (pintype "passive"))
      (node (ref "T10") (pin "1") (pinfunction "G_1") (pintype "passive"))
    )
    (net (code "100") (name "/PWM_C5") (class "Default")
      (node (ref "IC24") (pin "15") (pinfunction "PWM5_15") (pintype "output"))
      (node (ref "R139") (pin "2") (pinfunction "2_2") (pintype "passive"))
      (node (ref "T11") (pin "1") (pinfunction "G_1") (pintype "passive"))
    )
    (net (code "101") (name "/RESETn") (class "Default")
      (node (ref "J2") (pin "10") (pinfunction "10_10") (pintype "bidirectional"))
    )
    (net (code "120") (name "/SPI1_MISO") (class "Default")
      (node (ref "J2") (pin "8") (pinfunction "8_8") (pintype "bidirectional"))
    )
    (net (code "121") (name "/SPI1_MOSI") (class "Default")
      (node (ref "J2") (pin "6") (pinfunction "6_6") (pintype "bidirectional"))
    )
    (net (code "122") (name "/SPI1_NSS") (class "Default")
      (node (ref "J2") (pin "2") (pinfunction "2_2") (pintype "bidirectional"))
    )
    (net (code "123") (name "/SPI1_SCK") (class "Default")
      (node (ref "J2") (pin "4") (pinfunction "4_4") (pintype "bidirectional"))
    )
    (net (code "124") (name "/SWn1") (class "Default")
      (node (ref "J2") (pin "19") (pinfunction "19_19") (pintype "bidirectional"))
    )
    (net (code "125") (name "/SWn2") (class "Default")
      (node (ref "J2") (pin "20") (pinfunction "20_20") (pintype "bidirectional"))
    )
    (net (code "126") (name "/TACH1") (class "Default")
      (node (ref "IC24") (pin "6") (pinfunction "TACH1_6") (pintype "input"))
    )
    (net (code "128") (name "/TACH2") (class "Default")
      (node (ref "IC24") (pin "8") (pinfunction "TACH2_8") (pintype "input"))
    )
    (net (code "129") (name "/TACH3") (class "Default")
      (node (ref "IC24") (pin "10") (pinfunction "TACH3_10") (pintype "input"))
    )
    (net (code "130") (name "/TACH4") (class "Default")
      (node (ref "IC24") (pin "14") (pinfunction "TACH4_14") (pintype "input"))
    )
    (net (code "131") (name "/TACH5") (class "Default")
      (node (ref "IC24") (pin "16") (pinfunction "TACH5_16") (pintype "input"))
    )
    (net (code "132") (name "/THERMn") (class "Default")
      (node (ref "R22") (pin "2") (pinfunction "2_2") (pintype "passive"))
    )
    (net (code "133") (name "/USB_DM") (class "Default")
      (node (ref "J2") (pin "27") (pinfunction "27_27") (pintype "bidirectional"))
    )
    (net (code "134") (name "/USB_DP") (class "Default")
      (node (ref "J2") (pin "28") (pinfunction "28_28") (pintype "bidirectional"))
    )
    (net (code "135") (name "/USB_ID") (class "Default")
      (node (ref "J2") (pin "29") (pinfunction "29_29") (pintype "bidirectional"))
    )
    (net (code "136") (name "/USB_VBUS") (class "Default")
      (node (ref "J2") (pin "26") (pinfunction "26_26") (pintype "bidirectional"))
    )
    (net (code "137") (name "GND") (class "Default")
      (node (ref "C52") (pin "2") (pinfunction "2_2") (pintype "passive"))
      (node (ref "C53") (pin "2") (pinfunction "2_2") (pintype "passive"))
      (node (ref "C65") (pin "2") (pinfunction "2_2") (pintype "passive"))
      (node (ref "C88") (pin "1") (pinfunction "1_1") (pintype "passive"))
      (node (ref "D10") (pin "1") (pinfunction "GND_1") (pintype "power_in"))
      (node (ref "D11") (pin "1") (pinfunction "GND_1") (pintype "power_in"))
      (node (ref "D12") (pin "1") (pinfunction "GND_1") (pintype "power_in"))
      (node (ref "D13") (pin "1") (pinfunction "GND_1") (pintype "power_in"))
      (node (ref "D14") (pin "1") (pinfunction "GND_1") (pintype "power_in"))
      (node (ref "D7") (pin "1") (pinfunction "GND_1") (pintype "power_in"))
      (node (ref "D8") (pin "1") (pinfunction "GND_1") (pintype "power_in"))
      (node (ref "D9") (pin "1") (pinfunction "GND_1") (pintype "power_in"))
      (node (ref "IC10") (pin "3") (pinfunction "GND_3") (pintype "power_in"))
      (node (ref "IC11") (pin "25") (pinfunction "EP_25") (pintype "power_in"))
      (node (ref "IC11") (pin "9") (pinfunction "GND_9") (pintype "power_in"))
      (node (ref "IC24") (pin "17") (pinfunction "GND_17") (pintype "power_in"))
      (node (ref "J2") (pin "11") (pinfunction "11_11") (pintype "bidirectional"))
      (node (ref "J2") (pin "13") (pinfunction "13_13") (pintype "bidirectional"))
      (node (ref "J2") (pin "15") (pinfunction "15_15") (pintype "bidirectional"))
      (node (ref "J2") (pin "25") (pinfunction "25_25") (pintype "bidirectional"))
      (node (ref "J2") (pin "3") (pinfunction "3_3") (pintype "bidirectional"))
      (node (ref "J2") (pin "30") (pinfunction "30_30") (pintype "bidirectional"))
      (node (ref "J2") (pin "5") (pinfunction "5_5") (pintype "bidirectional"))
      (node (ref "J2") (pin "7") (pinfunction "7_7") (pintype "bidirectional"))
      (node (ref "J2") (pin "9") (pinfunction "9_9") (pintype "bidirectional"))
      (node (ref "J4") (pin "10") (pinfunction "10_10") (pintype "bidirectional"))
      (node (ref "R134") (pin "1") (pinfunction "1_1") (pintype "passive"))
      (node (ref "R135") (pin "1") (pinfunction "1_1") (pintype "passive"))
      (node (ref "R136") (pin "1") (pinfunction "1_1") (pintype "passive"))
      (node (ref "R137") (pin "1") (pinfunction "1_1") (pintype "passive"))
      (node (ref "R138") (pin "1") (pinfunction "1_1") (pintype "passive"))
      (node (ref "R139") (pin "1") (pinfunction "1_1") (pintype "passive"))
      (node (ref "R66") (pin "1") (pinfunction "1_1") (pintype "passive"))
      (node (ref "R67") (pin "1") (pinfunction "1_1") (pintype "passive"))
      (node (ref "R69") (pin "1") (pinfunction "1_1") (pintype "passive"))
      (node (ref "T10") (pin "2") (pinfunction "S_2") (pintype "passive"))
      (node (ref "T11") (pin "2") (pinfunction "S_2") (pintype "passive"))
      (node (ref "T7") (pin "2") (pinfunction "S_2") (pintype "passive"))
      (node (ref "T8") (pin "2") (pinfunction "S_2") (pintype "passive"))
      (node (ref "T9") (pin "2") (pinfunction "S_2") (pintype "passive"))
    )
    (net (code "138") (name "Net-(IC11-A0)") (class "Default")
      (node (ref "IC11") (pin "22") (pinfunction "A0_22") (pintype "input"))
      (node (ref "R69") (pin "2") (pinfunction "2_2") (pintype "passive"))
    )
    (net (code "139") (name "Net-(IC11-A1)") (class "Default")
      (node (ref "IC11") (pin "23") (pinfunction "A1_23") (pintype "input"))
      (node (ref "R67") (pin "2") (pinfunction "2_2") (pintype "passive"))
    )
    (net (code "140") (name "Net-(IC11-A2)") (class "Default")
      (node (ref "IC11") (pin "18") (pinfunction "A2_18") (pintype "input"))
      (node (ref "R66") (pin "2") (pinfunction "2_2") (pintype "passive"))
    )
    (net (code "141") (name "Net-(IC24-ADDR_SEL)") (class "Default")
      (node (ref "IC24") (pin "4") (pinfunction "ADDR_SEL_4") (pintype "bidirectional"))
      (node (ref "R137") (pin "2") (pinfunction "2_2") (pintype "passive"))
    )
    (net (code "142") (name "Net-(J2-Pad23)") (class "Default")
      (node (ref "J2") (pin "23") (pinfunction "23_23") (pintype "bidirectional"))
      (node (ref "R126") (pin "2") (pinfunction "2_2") (pintype "passive"))
    )
    (net (code "143") (name "Net-(J2-Pad24)") (class "Default")
      (node (ref "J2") (pin "24") (pinfunction "24_24") (pintype "bidirectional"))
      (node (ref "R127") (pin "2") (pinfunction "2_2") (pintype "passive"))
    )
    (net (code "144") (name "P3V3") (class "Default")
      (node (ref "C53") (pin "1") (pinfunction "1_1") (pintype "passive"))
      (node (ref "C65") (pin "1") (pinfunction "1_1") (pintype "passive"))
      (node (ref "C88") (pin "2") (pinfunction "2_2") (pintype "passive"))
      (node (ref "D10") (pin "4") (pinfunction "VCC_4") (pintype "power_in"))
      (node (ref "D11") (pin "4") (pinfunction "VCC_4") (pintype "power_in"))
      (node (ref "D12") (pin "4") (pinfunction "VCC_4") (pintype "power_in"))
      (node (ref "D13") (pin "4") (pinfunction "VCC_4") (pintype "power_in"))
      (node (ref "D14") (pin "4") (pinfunction "VCC_4") (pintype "power_in"))
      (node (ref "D7") (pin "4") (pinfunction "VCC_4") (pintype "power_in"))
      (node (ref "D8") (pin "4") (pinfunction "VCC_4") (pintype "power_in"))
      (node (ref "D9") (pin "4") (pinfunction "VCC_4") (pintype "power_in"))
      (node (ref "IC10") (pin "1") (pinfunction "Vin_1") (pintype "power_in"))
      (node (ref "IC11") (pin "21") (pinfunction "VCC_21") (pintype "power_in"))
      (node (ref "IC24") (pin "3") (pinfunction "VDD_3") (pintype "power_in"))
      (node (ref "J2") (pin "21") (pinfunction "21_21") (pintype "bidirectional"))
      (node (ref "J2") (pin "22") (pinfunction "22_22") (pintype "bidirectional"))
      (node (ref "R105") (pin "2") (pinfunction "2_2") (pintype "passive"))
      (node (ref "R22") (pin "1") (pinfunction "1_1") (pintype "passive"))
      (node (ref "R23") (pin "1") (pinfunction "1_1") (pintype "passive"))
      (node (ref "R24") (pin "1") (pinfunction "1_1") (pintype "passive"))
      (node (ref "R60") (pin "1") (pinfunction "1_1") (pintype "passive"))
      (node (ref "R61") (pin "2") (pinfunction "2_2") (pintype "passive"))
      (node (ref "R62") (pin "1") (pinfunction "1_1") (pintype "passive"))
      (node (ref "R63") (pin "2") (pinfunction "2_2") (pintype "passive"))
      (node (ref "R64") (pin "2") (pinfunction "2_2") (pintype "passive"))
      (node (ref "R65") (pin "2") (pinfunction "2_2") (pintype "passive"))
      (node (ref "R68") (pin "2") (pinfunction "2_2") (pintype "passive"))
      (node (ref "R70") (pin "2") (pinfunction "2_2") (pintype "passive"))
      (node (ref "R71") (pin "2") (pinfunction "2_2") (pintype "passive"))
      (node (ref "R72") (pin "2") (pinfunction "2_2") (pintype "passive"))
      (node (ref "R73") (pin "2") (pinfunction "2_2") (pintype "passive"))
      (node (ref "R74") (pin "2") (pinfunction "2_2") (pintype "passive"))
      (node (ref "R75") (pin "2") (pinfunction "2_2") (pintype "passive"))
      (node (ref "R76") (pin "2") (pinfunction "2_2") (pintype "passive"))
      (node (ref "R77") (pin "2") (pinfunction "2_2") (pintype "passive"))
      (node (ref "R78") (pin "2") (pinfunction "2_2") (pintype "passive"))
      (node (ref "R79") (pin "2") (pinfunction "2_2") (pintype "passive"))
      (node (ref "R80") (pin "2") (pinfunction "2_2") (pintype "passive"))
    )
    (net (code "145") (name "unconnected-(IC24-CLK-Pad11)") (class "Default")
      (node (ref "IC24") (pin "11") (pinfunction "CLK_11") (pintype "input+no_connect"))
    )
  )
)
